# ProDocument_V3_2024-06-08.net
KiCad netlist of a schematic drawn in EasyEDA Pro
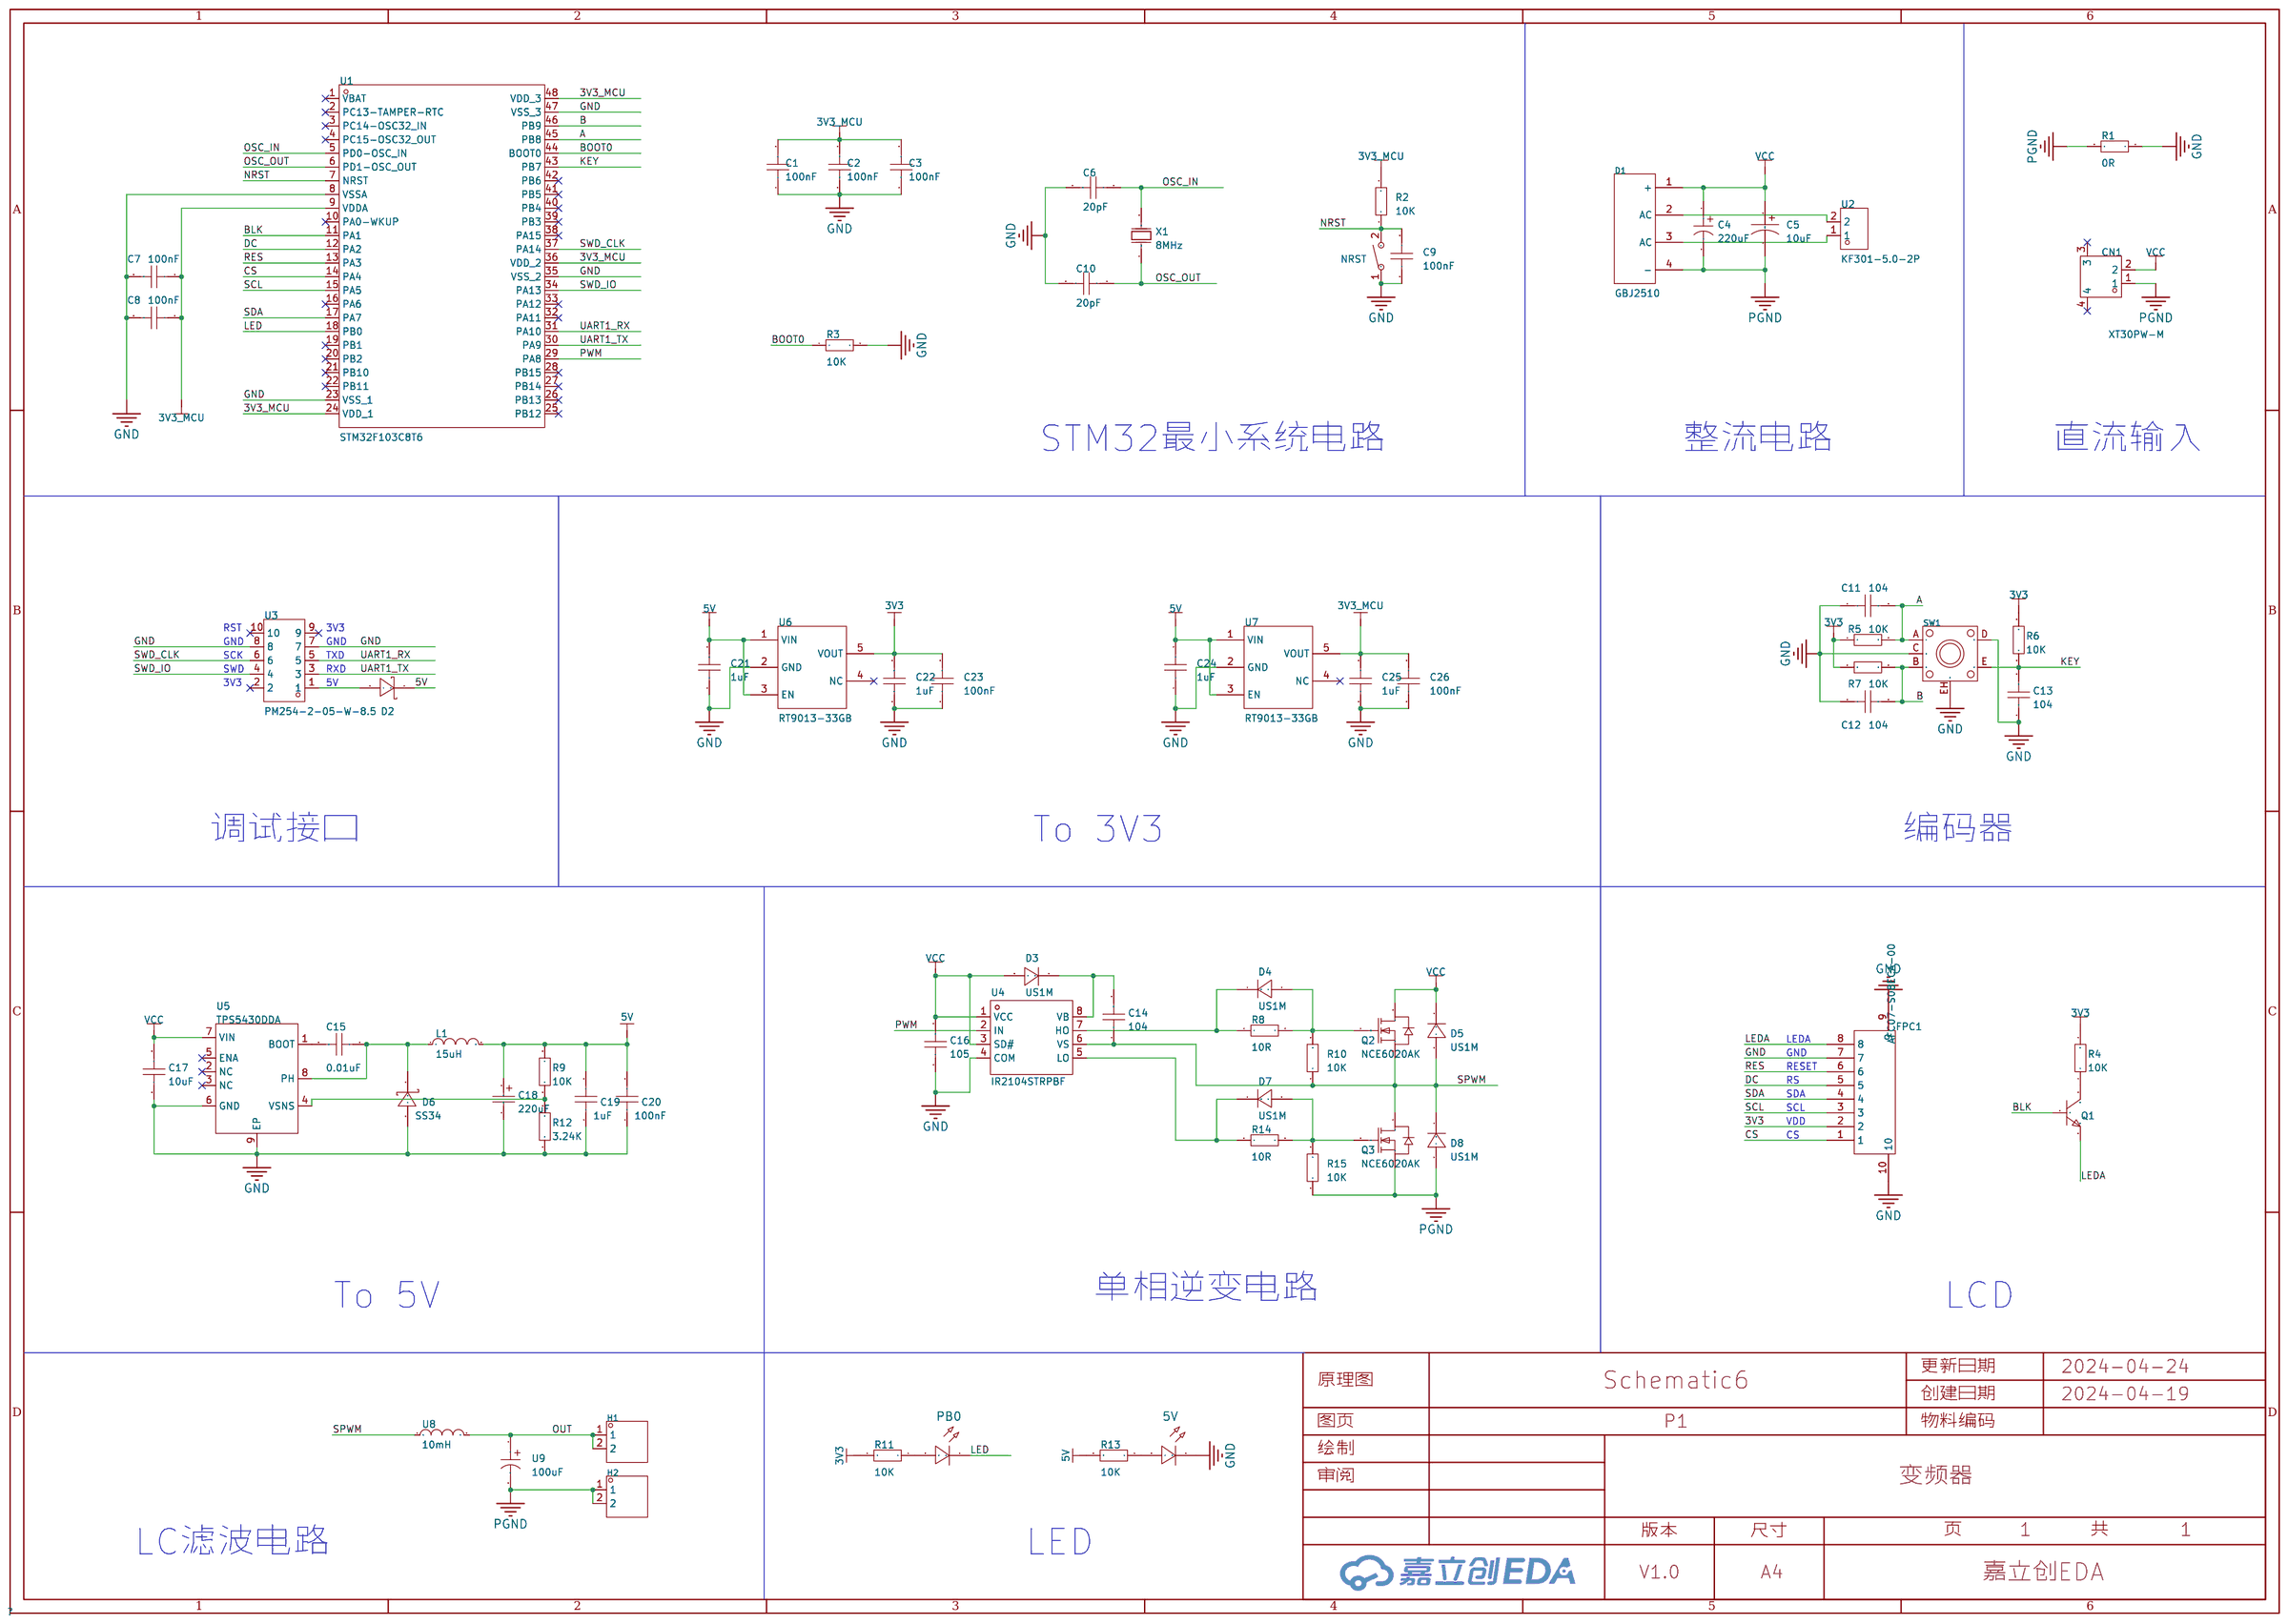
[diagram p0: schematic sheet]

(export (version "E")
  (design (tool "Eeschema 10.0.6"))
  (components
    (comp (ref "5V")
      (value "~")
      (footprint "easyedapro:LED_0603")
      (libsource (lib "easyedapro") (part "LED_R"))
    )
    (comp (ref "C1")
      (value "100nF")
      (footprint "easyedapro:C0603")
      (libsource (lib "easyedapro") (part "CapAcitance"))
    )
    (comp (ref "C2")
      (value "100nF")
      (footprint "easyedapro:C0603")
      (libsource (lib "easyedapro") (part "CapAcitance"))
    )
    (comp (ref "C3")
      (value "100nF")
      (footprint "easyedapro:C0603")
      (libsource (lib "easyedapro") (part "CapAcitance"))
    )
    (comp (ref "C4")
      (value "220uF")
      (footprint "easyedapro:CAP-TH_BD8.0-P3.50-D0.6-FD")
      (description "容值:220uF;精度:±20%;额定电压:50V;纹波电流:350mA@120kHz;等效串联电阻:-;")
      (fields (field (name "Manufacturer Part") "01EC3470") (field (name "Manufacturer") "KNSCHA(科尼盛)"))
      (libsource (lib "easyedapro") (part "01EC3470"))
    )
    (comp (ref "C5")
      (value "10uF")
      (footprint "easyedapro:CAP-TH_BD5.0-P2.00-D0.8-FD")
      (description "容值:10uF;精度:±20%;额定电压:50V;纹波电流:50mA@120Hz;等效串联电阻:-;")
      (fields
        (field (name "Manufacturer Part") "01EC1809SHC10UF50V")
        (field (name "Manufacturer") "KNSCHA(科尼盛)")
      )
      (libsource (lib "easyedapro") (part "01EC1809SHC10UF50V"))
    )
    (comp (ref "C6")
      (value "20pF")
      (footprint "easyedapro:C0603")
      (libsource (lib "easyedapro") (part "CapAcitance"))
    )
    (comp (ref "C7")
      (value "100nF")
      (footprint "easyedapro:C0603")
      (libsource (lib "easyedapro") (part "CapAcitance"))
    )
    (comp (ref "C8")
      (value "100nF")
      (footprint "easyedapro:C0603")
      (libsource (lib "easyedapro") (part "CapAcitance"))
    )
    (comp (ref "C9")
      (value "100nF")
      (footprint "easyedapro:C0603")
      (libsource (lib "easyedapro") (part "CapAcitance"))
    )
    (comp (ref "C10")
      (value "20pF")
      (footprint "easyedapro:C0603")
      (libsource (lib "easyedapro") (part "CapAcitance"))
    )
    (comp (ref "C11")
      (value "104")
      (footprint "easyedapro:C0603")
      (libsource (lib "easyedapro") (part "CapAcitance"))
    )
    (comp (ref "C12")
      (value "104")
      (footprint "easyedapro:C0603")
      (libsource (lib "easyedapro") (part "CapAcitance"))
    )
    (comp (ref "C13")
      (value "104")
      (footprint "easyedapro:C0603")
      (libsource (lib "easyedapro") (part "CapAcitance"))
    )
    (comp (ref "C14")
      (value "104")
      (footprint "easyedapro:C0603")
      (libsource (lib "easyedapro") (part "CapAcitance"))
    )
    (comp (ref "C15")
      (value "100nF")
      (footprint "easyedapro:C0603")
      (libsource (lib "easyedapro") (part "CapAcitance"))
    )
    (comp (ref "C16")
      (value "105")
      (footprint "easyedapro:C0603")
      (libsource (lib "easyedapro") (part "CapAcitance"))
    )
    (comp (ref "C17")
      (value "100nF")
      (footprint "easyedapro:C0603")
      (libsource (lib "easyedapro") (part "CapAcitance"))
    )
    (comp (ref "C18")
      (value "220uF")
      (footprint "easyedapro:CASE-D_7343")
      (description "容值:220uF;精度:±10%;额定电压:10V;等效串联电阻:500mΩ@100kHz;")
      (fields (field (name "Manufacturer Part") "TAJD227K010RNJ") (field (name "Manufacturer") "Kyocera AVX"))
      (libsource (lib "easyedapro") (part "TAJD227K010RNJ"))
    )
    (comp (ref "C19") (value "100nF") (libsource (lib "easyedapro") (part "c1210x7r475k630nt")))
    (comp (ref "C20") (value "100nF") (libsource (lib "easyedapro") (part "c1210x7r475k630nt")))
    (comp (ref "C21") (value "100nF") (libsource (lib "easyedapro") (part "c1210x7r475k630nt")))
    (comp (ref "C22") (value "100nF") (libsource (lib "easyedapro") (part "c1210x7r475k630nt")))
    (comp (ref "C23") (value "100nF") (libsource (lib "easyedapro") (part "c1210x7r475k630nt")))
    (comp (ref "C24") (value "100nF") (libsource (lib "easyedapro") (part "c1210x7r475k630nt")))
    (comp (ref "C25") (value "100nF") (libsource (lib "easyedapro") (part "c1210x7r475k630nt")))
    (comp (ref "C26") (value "100nF") (libsource (lib "easyedapro") (part "c1210x7r475k630nt")))
    (comp (ref "CN1")
      (value "XT30PW-M")
      (footprint "easyedapro:CONN-TH_XT30PW-M")
      (description "Socket,DCsupply,XT30,male,PIN:2")
      (fields (field (name "Manufacturer") "AMASS(艾迈斯)"))
      (libsource (lib "easyedapro") (part "XT30PW-M"))
    )
    (comp (ref "D1")
      (value "GBJ2510")
      (footprint "easyedapro:DIO-BG-TH_PB")
      (description "正向压降(Vf):1.05V@12.5A;直流反向耐压(Vr):1kV;平均整流电流(Io):25A;正向浪涌电流(Ifsm):350A;")
      (fields (field (name "Manufacturer") "MDD"))
      (libsource (lib "easyedapro") (part "GBJ2510"))
    )
    (comp (ref "D2")
      (value "1N5819WS")
      (footprint "easyedapro:SOD-323_L1.8-W1.3-LS2.5-RD")
      (description "正向压降(Vf):600mV@1A;直流反向耐压(Vr):40V;平均整流电流(Io):1A;")
      (fields (field (name "Manufacturer") "Hottech(合科泰)"))
      (libsource (lib "easyedapro") (part "1N5819WS"))
    )
    (comp (ref "D3")
      (value "US1M")
      (footprint "easyedapro:SMA_L4.4-W2.8-LS5.4-RD")
      (description "二极管配置:独立式;正向压降(Vf):1.7V@1A;直流反向耐压(Vr):1kV;平均整流电流(Io):1A;反向恢复时间(trr):75ns;")
      (fields (field (name "Manufacturer") "MDD"))
      (libsource (lib "easyedapro") (part "US1MG_C412437"))
    )
    (comp (ref "D4")
      (value "US1M")
      (footprint "easyedapro:SMA_L4.4-W2.8-LS5.4-RD")
      (description "二极管配置:独立式;正向压降(Vf):1.7V@1A;直流反向耐压(Vr):1kV;平均整流电流(Io):1A;反向恢复时间(trr):75ns;")
      (fields (field (name "Manufacturer") "MDD"))
      (libsource (lib "easyedapro") (part "US1MG_C412437"))
    )
    (comp (ref "D5")
      (value "US1M")
      (footprint "easyedapro:SMA_L4.4-W2.8-LS5.4-RD")
      (description "二极管配置:独立式;正向压降(Vf):1.7V@1A;直流反向耐压(Vr):1kV;平均整流电流(Io):1A;反向恢复时间(trr):75ns;")
      (fields (field (name "Manufacturer") "MDD"))
      (libsource (lib "easyedapro") (part "US1MG_C412437"))
    )
    (comp (ref "D6")
      (value "SS34")
      (footprint "easyedapro:SMA_L4.3-W2.6-LS5.2-RD")
      (description "二极管配置:独立式;直流反向耐压(Vr):40V;平均整流电流(Io):3A;正向压降(Vf):550mV@3A;反向电流(Ir):500uA@40V;")
      (fields (field (name "Manufacturer") "MDD"))
      (libsource (lib "easyedapro") (part "SS34_C8678"))
    )
    (comp (ref "D7")
      (value "US1M")
      (footprint "easyedapro:SMA_L4.4-W2.8-LS5.4-RD")
      (description "二极管配置:独立式;正向压降(Vf):1.7V@1A;直流反向耐压(Vr):1kV;平均整流电流(Io):1A;反向恢复时间(trr):75ns;")
      (fields (field (name "Manufacturer") "MDD"))
      (libsource (lib "easyedapro") (part "US1MG_C412437"))
    )
    (comp (ref "D8")
      (value "US1M")
      (footprint "easyedapro:SMA_L4.4-W2.8-LS5.4-RD")
      (description "二极管配置:独立式;正向压降(Vf):1.7V@1A;直流反向耐压(Vr):1kV;平均整流电流(Io):1A;反向恢复时间(trr):75ns;")
      (fields (field (name "Manufacturer") "MDD"))
      (libsource (lib "easyedapro") (part "US1MG_C412437"))
    )
    (comp (ref "FPC1")
      (value "AFC07-S08ECA-00")
      (footprint "easyedapro:FPC-SMD_P0.5-8P_LCS-SH-H2.0")
      (description "间距:0.5mm;触点数量:8P;锁定特性:抽屉式;触点类型:上接;安装类型:卧贴;")
      (fields (field (name "Manufacturer") "JS(钜硕电子)"))
      (libsource (lib "easyedapro") (part "AFC07-S08ECA-00"))
    )
    (comp (ref "H1")
      (value "~")
      (footprint "easyedapro:HDR-TH_2P-P2.54-V-M-1")
      (libsource (lib "easyedapro") (part "210S-1*2P L=11.6MMGold-plated black"))
    )
    (comp (ref "H2")
      (value "~")
      (footprint "easyedapro:HDR-TH_2P-P2.54-V-M-1")
      (libsource (lib "easyedapro") (part "210S-1*2P L=11.6MMGold-plated black"))
    )
    (comp (ref "L1")
      (value "15uH")
      (footprint "easyedapro:IND-SMD_L7.0-W6.6_FXL0630")
      (description "电感值:15uH;精度:±20%;额定电流:3A;饱和电流(Isat):4.5A;类型:一体成型电感;")
      (fields (field (name "Manufacturer Part") "FXL0630-150-M") (field (name "Manufacturer") "cjiang(长江微电)"))
      (libsource (lib "easyedapro") (part "FXL0630-150-M"))
    )
    (comp (ref "NRST")
      (value "TS-1071AD-A1B3-D4")
      (footprint "easyedapro:SW-SMD_L4.0-W3.0-LS4.8")
      (description "电路结构:单刀单掷;按钮形状:圆形按钮;作用力:250gf;安装方式:-;开关长度:4mm;开关宽度:3mm;开关高度:2mm;带灯:-;机械寿命:-;")
      (fields (field (name "Manufacturer") "Yuandi(元迪)"))
      (libsource (lib "easyedapro") (part "TS-1071AD-A1B3-D4"))
    )
    (comp (ref "PB0")
      (value "~")
      (footprint "easyedapro:LED_0603")
      (libsource (lib "easyedapro") (part "LED_R"))
    )
    (comp (ref "Q1")
      (value "~")
      (footprint "easyedapro:S8050_SOT-23")
      (libsource (lib "easyedapro") (part "NPN"))
    )
    (comp (ref "Q2")
      (value "NCE6020AK")
      (footprint "easyedapro:TO-252-2_L6.6-W6.1-P4.57-LS10.1-TL-CW")
      (fields (field (name "Manufacturer") "NCE(无锡新洁能)"))
      (libsource (lib "easyedapro") (part "NCE6020AK"))
    )
    (comp (ref "Q3")
      (value "NCE6020AK")
      (footprint "easyedapro:TO-252-2_L6.6-W6.1-P4.57-LS10.1-TL-CW")
      (fields (field (name "Manufacturer") "NCE(无锡新洁能)"))
      (libsource (lib "easyedapro") (part "NCE6020AK"))
    )
    (comp (ref "R1") (value "0R") (footprint "easyedapro:R0603") (libsource (lib "easyedapro") (part "电阻")))
    (comp (ref "R2") (value "10K") (footprint "easyedapro:R0603") (libsource (lib "easyedapro") (part "电阻")))
    (comp (ref "R3") (value "10K") (footprint "easyedapro:R0603") (libsource (lib "easyedapro") (part "电阻")))
    (comp (ref "R4") (value "10K") (footprint "easyedapro:R0603") (libsource (lib "easyedapro") (part "电阻")))
    (comp (ref "R5") (value "10K") (footprint "easyedapro:R0603") (libsource (lib "easyedapro") (part "电阻")))
    (comp (ref "R6") (value "10K") (footprint "easyedapro:R0603") (libsource (lib "easyedapro") (part "电阻")))
    (comp (ref "R7") (value "10K") (footprint "easyedapro:R0603") (libsource (lib "easyedapro") (part "电阻")))
    (comp (ref "R8") (value "10R") (footprint "easyedapro:R0603") (libsource (lib "easyedapro") (part "电阻")))
    (comp (ref "R9") (value "10K") (footprint "easyedapro:R0603") (libsource (lib "easyedapro") (part "电阻")))
    (comp (ref "R10") (value "10K") (footprint "easyedapro:R0603") (libsource (lib "easyedapro") (part "电阻")))
    (comp (ref "R11") (value "10K") (footprint "easyedapro:R0603") (libsource (lib "easyedapro") (part "电阻")))
    (comp (ref "R12") (value "10K") (footprint "easyedapro:R0603") (libsource (lib "easyedapro") (part "电阻")))
    (comp (ref "R13") (value "10K") (footprint "easyedapro:R0603") (libsource (lib "easyedapro") (part "电阻")))
    (comp (ref "R14") (value "10R") (footprint "easyedapro:R0603") (libsource (lib "easyedapro") (part "电阻")))
    (comp (ref "R15") (value "10K") (footprint "easyedapro:R0603") (libsource (lib "easyedapro") (part "电阻")))
    (comp (ref "SW1")
      (value "EC11N1520401")
      (footprint "easyedapro:SW-TH_EC11NXXXX")
      (fields (field (name "Manufacturer") "ALPSALPINE(阿尔卑斯阿尔派)"))
      (libsource (lib "easyedapro") (part "EC11N1520401"))
    )
    (comp (ref "U1")
      (value "STM32F103C8T6")
      (footprint "easyedapro:LQFP-48_L7.0-W7.0-P0.50-LS9.0-BL")
      (description "CPU内核:CM3;程序存储容量:64KB;RAM总容量:20KB;GPIO端口数量:37;工作电压范围:2V~3.6V;CPU最大主频:72MHz;程序存储器类型:FLASH;")
      (fields (field (name "Manufacturer") "ST(意法半导体)"))
      (libsource (lib "easyedapro") (part "STM32F103C8T6"))
    )
    (comp (ref "U2")
      (value "KF301-5.0-2P")
      (footprint "easyedapro:CONN-TH_P5.00_KF301-5.0-2P")
      (fields (field (name "Manufacturer") "KEFA(科发)"))
      (libsource (lib "easyedapro") (part "KF301-5.0-2P"))
    )
    (comp (ref "U3")
      (value "PM254-2-05-W-8.5")
      (footprint "easyedapro:HDR-TH_10P-P2.54-H-F-R2-C5-W8.5")
      (fields (field (name "Manufacturer") "HCTL(华灿天禄)"))
      (libsource (lib "easyedapro") (part "PM254-2-05-W-8.5"))
    )
    (comp (ref "U4")
      (value "IR2104STRPBF")
      (footprint "easyedapro:SOIC-8_L4.9-W3.9-P1.27-LS6.0-BL")
      (description "驱动配置:半桥;负载类型:MOSFET；IGBT;驱动通道数:2;峰值灌电流:360mA;峰值拉电流:210mA;电源电压:10V~20V;上升时间:100ns;下降时间:50ns;")
      (fields (field (name "Manufacturer") "Infineon(英飞凌)"))
      (libsource (lib "easyedapro") (part "IR2104STRPBF"))
    )
    (comp (ref "U5")
      (value "TPS5430DDA")
      (footprint "easyedapro:ESOP-8_L4.9-W3.9-P1.27-LS6.0-BL-EP-2")
      (fields (field (name "Manufacturer") "TI(德州仪器)"))
      (libsource (lib "easyedapro") (part "TPS5430DDA"))
    )
    (comp (ref "U6")
      (value "RT9013-33GB")
      (footprint "easyedapro:SOT-23-5_L3.0-W1.7-P0.95-LS2.8-BL")
      (description "输出类型:固定;最大输入电压:5.5V;输出电压:3.3V;最大输出电流:500mA;电源纹波抑制比(PSRR):50dB@(10kHz);输出极性:正极;")
      (fields (field (name "Manufacturer") "RICHTEK(立锜)"))
      (libsource (lib "easyedapro") (part "RT9013-33GB"))
    )
    (comp (ref "U7")
      (value "RT9013-33GB")
      (footprint "easyedapro:SOT-23-5_L3.0-W1.7-P0.95-LS2.8-BL")
      (description "输出类型:固定;最大输入电压:5.5V;输出电压:3.3V;最大输出电流:500mA;电源纹波抑制比(PSRR):50dB@(10kHz);输出极性:正极;")
      (fields (field (name "Manufacturer") "RICHTEK(立锜)"))
      (libsource (lib "easyedapro") (part "RT9013-33GB"))
    )
    (comp (ref "U8")
      (value "10mH")
      (footprint "easyedapro:IND-TH_BD10.0-P5.00-D0.6")
      (description "电感值:100uH;精度:±10%;类型:工字电感;")
      (fields (field (name "Manufacturer Part") "XR8*10-101K-L") (field (name "Manufacturer") "XR(祥如)"))
      (libsource (lib "easyedapro") (part "XR8*10-101K-L"))
    )
    (comp (ref "U9")
      (value "100uF")
      (footprint "easyedapro:CAP-TH_BD8.0-P3.50-D0.6-FD")
      (description "容值:470uF;精度:±20%;额定电压:16V;")
      (fields (field (name "Manufacturer Part") "8471LCM0812LEN91EC") (field (name "Manufacturer") "FH(风华)"))
      (libsource (lib "easyedapro") (part "8471LCM0812LEN91EC"))
    )
    (comp (ref "X1")
      (value "8MHz")
      (footprint "easyedapro:CRYSTAL-SMD_L5.0-W3.2")
      (description "晶振类型:贴片晶振;频率:8MHz;常温频差:±10ppm;外接负载电容:20pF;频率稳定度(全温):±20ppm;")
      (fields (field (name "Manufacturer Part") "X50328MSB2GI") (field (name "Manufacturer") "YXC(扬兴晶振)"))
      (libsource (lib "easyedapro") (part "X50328MSB2GI"))
    )
  )
  (nets
    (net (code "1") (name "/A") (class "Default")
      (node (ref "C11") (pin "2") (pinfunction "2_2") (pintype "input"))
      (node (ref "R5") (pin "2") (pinfunction "2_2") (pintype "input"))
      (node (ref "SW1") (pin "A") (pinfunction "A_A") (pintype "input"))
      (node (ref "U1") (pin "45") (pinfunction "PB8_45") (pintype "unspecified"))
    )
    (net (code "2") (name "/B") (class "Default")
      (node (ref "C12") (pin "2") (pinfunction "2_2") (pintype "input"))
      (node (ref "R7") (pin "2") (pinfunction "2_2") (pintype "input"))
      (node (ref "SW1") (pin "B") (pinfunction "B_B") (pintype "input"))
      (node (ref "U1") (pin "46") (pinfunction "PB9_46") (pintype "unspecified"))
    )
    (net (code "3") (name "/BLK") (class "Default")
      (node (ref "Q1") (pin "1") (pinfunction "1_1") (pintype "unspecified"))
      (node (ref "U1") (pin "11") (pinfunction "PA1_11") (pintype "unspecified"))
    )
    (net (code "4") (name "/BOOT0") (class "Default")
      (node (ref "R3") (pin "1") (pinfunction "1_1") (pintype "input"))
      (node (ref "U1") (pin "44") (pinfunction "BOOT0_44") (pintype "unspecified"))
    )
    (net (code "5") (name "/CS") (class "Default")
      (node (ref "FPC1") (pin "1") (pinfunction "1_1") (pintype "unspecified"))
      (node (ref "U1") (pin "14") (pinfunction "PA4_14") (pintype "unspecified"))
    )
    (net (code "6") (name "/DC") (class "Default")
      (node (ref "FPC1") (pin "5") (pinfunction "5_5") (pintype "unspecified"))
      (node (ref "U1") (pin "12") (pinfunction "PA2_12") (pintype "unspecified"))
    )
    (net (code "7") (name "/KEY") (class "Default")
      (node (ref "C13") (pin "2") (pinfunction "2_2") (pintype "input"))
      (node (ref "R6") (pin "1") (pinfunction "1_1") (pintype "input"))
      (node (ref "SW1") (pin "E") (pinfunction "E_E") (pintype "input"))
      (node (ref "U1") (pin "43") (pinfunction "PB7_43") (pintype "unspecified"))
    )
    (net (code "8") (name "/LED") (class "Default")
      (node (ref "PB0") (pin "1") (pinfunction "C_1") (pintype "input"))
      (node (ref "U1") (pin "18") (pinfunction "PB0_18") (pintype "unspecified"))
    )
    (net (code "9") (name "/LEDA") (class "Default")
      (node (ref "FPC1") (pin "8") (pinfunction "8_8") (pintype "unspecified"))
      (node (ref "Q1") (pin "2") (pinfunction "2_2") (pintype "unspecified"))
    )
    (net (code "10") (name "/NRST") (class "Default")
      (node (ref "C9") (pin "2") (pinfunction "2_2") (pintype "input"))
      (node (ref "NRST") (pin "2") (pinfunction "2_2") (pintype "unspecified"))
      (node (ref "R2") (pin "1") (pinfunction "1_1") (pintype "input"))
      (node (ref "U1") (pin "7") (pinfunction "NRST_7") (pintype "unspecified"))
    )
    (net (code "11") (name "/OSC_IN") (class "Default")
      (node (ref "C6") (pin "1") (pinfunction "1_1") (pintype "input"))
      (node (ref "U1") (pin "5") (pinfunction "PD0-OSC_IN_5") (pintype "unspecified"))
      (node (ref "X1") (pin "2") (pinfunction "OSC2_2") (pintype "input"))
    )
    (net (code "12") (name "/OSC_OUT") (class "Default")
      (node (ref "C10") (pin "1") (pinfunction "1_1") (pintype "input"))
      (node (ref "U1") (pin "6") (pinfunction "PD1-OSC_OUT_6") (pintype "unspecified"))
      (node (ref "X1") (pin "1") (pinfunction "OSC1_1") (pintype "input"))
    )
    (net (code "13") (name "/OUT") (class "Default")
      (node (ref "H1") (pin "1") (pinfunction "1_1") (pintype "input"))
      (node (ref "H1") (pin "2") (pinfunction "2_2") (pintype "input"))
      (node (ref "U8") (pin "2") (pinfunction "2_2") (pintype "unspecified"))
      (node (ref "U9") (pin "1") (pinfunction "1_1") (pintype "input"))
    )
    (net (code "14") (name "/PWM") (class "Default")
      (node (ref "U1") (pin "29") (pinfunction "PA8_29") (pintype "unspecified"))
      (node (ref "U4") (pin "2") (pinfunction "IN_2") (pintype "unspecified"))
    )
    (net (code "15") (name "/RES") (class "Default")
      (node (ref "FPC1") (pin "6") (pinfunction "6_6") (pintype "unspecified"))
      (node (ref "U1") (pin "13") (pinfunction "PA3_13") (pintype "unspecified"))
    )
    (net (code "16") (name "/SCL") (class "Default")
      (node (ref "FPC1") (pin "3") (pinfunction "3_3") (pintype "unspecified"))
      (node (ref "U1") (pin "15") (pinfunction "PA5_15") (pintype "unspecified"))
    )
    (net (code "17") (name "/SDA") (class "Default")
      (node (ref "FPC1") (pin "4") (pinfunction "4_4") (pintype "unspecified"))
      (node (ref "U1") (pin "17") (pinfunction "PA7_17") (pintype "unspecified"))
    )
    (net (code "18") (name "/SPWM") (class "Default")
      (node (ref "C14") (pin "1") (pinfunction "1_1") (pintype "input"))
      (node (ref "D5") (pin "2") (pinfunction "A_2") (pintype "unspecified"))
      (node (ref "D8") (pin "1") (pinfunction "C_1") (pintype "unspecified"))
      (node (ref "Q2") (pin "3") (pinfunction "S_3") (pintype "input"))
      (node (ref "Q3") (pin "2") (pinfunction "D_2") (pintype "input"))
      (node (ref "R10") (pin "1") (pinfunction "1_1") (pintype "input"))
      (node (ref "U4") (pin "6") (pinfunction "VS_6") (pintype "unspecified"))
      (node (ref "U8") (pin "1") (pinfunction "1_1") (pintype "unspecified"))
    )
    (net (code "19") (name "/SWD_CLK") (class "Default")
      (node (ref "U1") (pin "37") (pinfunction "PA14_37") (pintype "unspecified"))
      (node (ref "U3") (pin "6") (pinfunction "6_6") (pintype "unspecified"))
    )
    (net (code "20") (name "/SWD_IO") (class "Default")
      (node (ref "U1") (pin "34") (pinfunction "PA13_34") (pintype "unspecified"))
      (node (ref "U3") (pin "4") (pinfunction "4_4") (pintype "unspecified"))
    )
    (net (code "21") (name "/UART1_RX") (class "Default")
      (node (ref "U1") (pin "31") (pinfunction "PA10_31") (pintype "unspecified"))
      (node (ref "U3") (pin "5") (pinfunction "5_5") (pintype "unspecified"))
    )
    (net (code "22") (name "/UART1_TX") (class "Default")
      (node (ref "U1") (pin "30") (pinfunction "PA9_30") (pintype "unspecified"))
      (node (ref "U3") (pin "3") (pinfunction "3_3") (pintype "unspecified"))
    )
    (net (code "23") (name "3V3") (class "Default")
      (node (ref "C22") (pin "2") (pinfunction "2_2") (pintype "input"))
      (node (ref "C23") (pin "2") (pinfunction "2_2") (pintype "input"))
      (node (ref "FPC1") (pin "2") (pinfunction "2_2") (pintype "unspecified"))
      (node (ref "R11") (pin "2") (pinfunction "2_2") (pintype "input"))
      (node (ref "R4") (pin "2") (pinfunction "2_2") (pintype "input"))
      (node (ref "R5") (pin "1") (pinfunction "1_1") (pintype "input"))
      (node (ref "R6") (pin "2") (pinfunction "2_2") (pintype "input"))
      (node (ref "R7") (pin "1") (pinfunction "1_1") (pintype "input"))
      (node (ref "U6") (pin "5") (pinfunction "VOUT_5") (pintype "unspecified"))
    )
    (net (code "24") (name "3V3_MCU") (class "Default")
      (node (ref "C1") (pin "2") (pinfunction "2_2") (pintype "input"))
      (node (ref "C2") (pin "2") (pinfunction "2_2") (pintype "input"))
      (node (ref "C25") (pin "2") (pinfunction "2_2") (pintype "input"))
      (node (ref "C26") (pin "2") (pinfunction "2_2") (pintype "input"))
      (node (ref "C3") (pin "2") (pinfunction "2_2") (pintype "input"))
      (node (ref "C7") (pin "1") (pinfunction "1_1") (pintype "input"))
      (node (ref "C8") (pin "1") (pinfunction "1_1") (pintype "input"))
      (node (ref "R2") (pin "2") (pinfunction "2_2") (pintype "input"))
      (node (ref "U1") (pin "24") (pinfunction "VDD_1_24") (pintype "unspecified"))
      (node (ref "U1") (pin "36") (pinfunction "VDD_2_36") (pintype "unspecified"))
      (node (ref "U1") (pin "48") (pinfunction "VDD_3_48") (pintype "unspecified"))
      (node (ref "U1") (pin "9") (pinfunction "VDDA_9") (pintype "unspecified"))
      (node (ref "U7") (pin "5") (pinfunction "VOUT_5") (pintype "unspecified"))
    )
    (net (code "25") (name "5V") (class "Default")
      (node (ref "C18") (pin "1") (pinfunction "1_1") (pintype "input"))
      (node (ref "C19") (pin "2") (pinfunction "2_2") (pintype "input"))
      (node (ref "C20") (pin "2") (pinfunction "2_2") (pintype "input"))
      (node (ref "C21") (pin "2") (pinfunction "2_2") (pintype "input"))
      (node (ref "C24") (pin "2") (pinfunction "2_2") (pintype "input"))
      (node (ref "D2") (pin "1") (pinfunction "K_1") (pintype "unspecified"))
      (node (ref "L1") (pin "2") (pinfunction "2_2") (pintype "unspecified"))
      (node (ref "R13") (pin "2") (pinfunction "2_2") (pintype "input"))
      (node (ref "R9") (pin "2") (pinfunction "2_2") (pintype "input"))
      (node (ref "U6") (pin "1") (pinfunction "VIN_1") (pintype "unspecified"))
      (node (ref "U6") (pin "3") (pinfunction "EN_3") (pintype "unspecified"))
      (node (ref "U7") (pin "1") (pinfunction "VIN_1") (pintype "unspecified"))
      (node (ref "U7") (pin "3") (pinfunction "EN_3") (pintype "unspecified"))
    )
    (net (code "26") (name "GND") (class "Default")
      (node (ref "5V") (pin "1") (pinfunction "C_1") (pintype "input"))
      (node (ref "C1") (pin "1") (pinfunction "1_1") (pintype "input"))
      (node (ref "C10") (pin "2") (pinfunction "2_2") (pintype "input"))
      (node (ref "C11") (pin "1") (pinfunction "1_1") (pintype "input"))
      (node (ref "C12") (pin "1") (pinfunction "1_1") (pintype "input"))
      (node (ref "C13") (pin "1") (pinfunction "1_1") (pintype "input"))
      (node (ref "C16") (pin "1") (pinfunction "1_1") (pintype "input"))
      (node (ref "C17") (pin "1") (pinfunction "1_1") (pintype "input"))
      (node (ref "C18") (pin "2") (pinfunction "2_2") (pintype "input"))
      (node (ref "C19") (pin "1") (pinfunction "1_1") (pintype "input"))
      (node (ref "C2") (pin "1") (pinfunction "1_1") (pintype "input"))
      (node (ref "C20") (pin "1") (pinfunction "1_1") (pintype "input"))
      (node (ref "C21") (pin "1") (pinfunction "1_1") (pintype "input"))
      (node (ref "C22") (pin "1") (pinfunction "1_1") (pintype "input"))
      (node (ref "C23") (pin "1") (pinfunction "1_1") (pintype "input"))
      (node (ref "C24") (pin "1") (pinfunction "1_1") (pintype "input"))
      (node (ref "C25") (pin "1") (pinfunction "1_1") (pintype "input"))
      (node (ref "C26") (pin "1") (pinfunction "1_1") (pintype "input"))
      (node (ref "C3") (pin "1") (pinfunction "1_1") (pintype "input"))
      (node (ref "C6") (pin "2") (pinfunction "2_2") (pintype "input"))
      (node (ref "C7") (pin "2") (pinfunction "2_2") (pintype "input"))
      (node (ref "C8") (pin "2") (pinfunction "2_2") (pintype "input"))
      (node (ref "C9") (pin "1") (pinfunction "1_1") (pintype "input"))
      (node (ref "D6") (pin "2") (pinfunction "A_2") (pintype "input"))
      (node (ref "FPC1") (pin "10") (pinfunction "10_10") (pintype "unspecified"))
      (node (ref "FPC1") (pin "7") (pinfunction "7_7") (pintype "unspecified"))
      (node (ref "FPC1") (pin "9") (pinfunction "9_9") (pintype "unspecified"))
      (node (ref "NRST") (pin "1") (pinfunction "1_1") (pintype "unspecified"))
      (node (ref "R1") (pin "1") (pinfunction "1_1") (pintype "input"))
      (node (ref "R12") (pin "1") (pinfunction "1_1") (pintype "input"))
      (node (ref "R3") (pin "2") (pinfunction "2_2") (pintype "input"))
      (node (ref "SW1") (pin "C") (pinfunction "C_C") (pintype "input"))
      (node (ref "SW1") (pin "D") (pinfunction "D_D") (pintype "input"))
      (node (ref "SW1") (pin "EH") (pinfunction "EH_EH") (pintype "input"))
      (node (ref "U1") (pin "23") (pinfunction "VSS_1_23") (pintype "unspecified"))
      (node (ref "U1") (pin "35") (pinfunction "VSS_2_35") (pintype "unspecified"))
      (node (ref "U1") (pin "47") (pinfunction "VSS_3_47") (pintype "unspecified"))
      (node (ref "U1") (pin "8") (pinfunction "VSSA_8") (pintype "unspecified"))
      (node (ref "U3") (pin "7") (pinfunction "7_7") (pintype "unspecified"))
      (node (ref "U3") (pin "8") (pinfunction "8_8") (pintype "unspecified"))
      (node (ref "U4") (pin "4") (pinfunction "COM_4") (pintype "unspecified"))
      (node (ref "U5") (pin "6") (pinfunction "GND_6") (pintype "input"))
      (node (ref "U5") (pin "9") (pinfunction "EP_9") (pintype "input"))
      (node (ref "U6") (pin "2") (pinfunction "GND_2") (pintype "unspecified"))
      (node (ref "U7") (pin "2") (pinfunction "GND_2") (pintype "unspecified"))
    )
    (net (code "27") (name "Net-(5V-A)") (class "Default")
      (node (ref "5V") (pin "2") (pinfunction "A_2") (pintype "input"))
      (node (ref "R13") (pin "1") (pinfunction "1_1") (pintype "input"))
    )
    (net (code "28") (name "Net-(D1-AC-Pad2)") (class "Default")
      (node (ref "D1") (pin "2") (pinfunction "AC_2") (pintype "input"))
      (node (ref "U2") (pin "2") (pinfunction "2_2") (pintype "unspecified"))
    )
    (net (code "29") (name "Net-(D1-AC-Pad3)") (class "Default")
      (node (ref "D1") (pin "3") (pinfunction "AC_3") (pintype "input"))
      (node (ref "U2") (pin "1") (pinfunction "1_1") (pintype "unspecified"))
    )
    (net (code "30") (name "Net-(D2-A)") (class "Default")
      (node (ref "D2") (pin "2") (pinfunction "A_2") (pintype "unspecified"))
      (node (ref "U3") (pin "1") (pinfunction "1_1") (pintype "unspecified"))
    )
    (net (code "31") (name "Net-(D3-C)") (class "Default")
      (node (ref "C14") (pin "2") (pinfunction "2_2") (pintype "input"))
      (node (ref "D3") (pin "1") (pinfunction "C_1") (pintype "unspecified"))
      (node (ref "U4") (pin "8") (pinfunction "VB_8") (pintype "unspecified"))
    )
    (net (code "32") (name "Net-(D4-A)") (class "Default")
      (node (ref "D4") (pin "2") (pinfunction "A_2") (pintype "unspecified"))
      (node (ref "Q2") (pin "1") (pinfunction "G_1") (pintype "input"))
      (node (ref "R10") (pin "2") (pinfunction "2_2") (pintype "input"))
      (node (ref "R8") (pin "2") (pinfunction "2_2") (pintype "input"))
    )
    (net (code "33") (name "Net-(D4-C)") (class "Default")
      (node (ref "D4") (pin "1") (pinfunction "C_1") (pintype "unspecified"))
      (node (ref "R8") (pin "1") (pinfunction "1_1") (pintype "input"))
      (node (ref "U4") (pin "7") (pinfunction "HO_7") (pintype "unspecified"))
    )
    (net (code "34") (name "Net-(D6-K)") (class "Default")
      (node (ref "C15") (pin "1") (pinfunction "1_1") (pintype "input"))
      (node (ref "D6") (pin "1") (pinfunction "K_1") (pintype "input"))
      (node (ref "L1") (pin "1") (pinfunction "1_1") (pintype "unspecified"))
      (node (ref "U5") (pin "8") (pinfunction "PH_8") (pintype "input"))
    )
    (net (code "35") (name "Net-(D7-A)") (class "Default")
      (node (ref "D7") (pin "2") (pinfunction "A_2") (pintype "unspecified"))
      (node (ref "Q3") (pin "1") (pinfunction "G_1") (pintype "input"))
      (node (ref "R14") (pin "2") (pinfunction "2_2") (pintype "input"))
      (node (ref "R15") (pin "2") (pinfunction "2_2") (pintype "input"))
    )
    (net (code "36") (name "Net-(D7-C)") (class "Default")
      (node (ref "D7") (pin "1") (pinfunction "C_1") (pintype "unspecified"))
      (node (ref "R14") (pin "1") (pinfunction "1_1") (pintype "input"))
      (node (ref "U4") (pin "5") (pinfunction "LO_5") (pintype "unspecified"))
    )
    (net (code "37") (name "Net-(PB0-A)") (class "Default")
      (node (ref "PB0") (pin "2") (pinfunction "A_2") (pintype "input"))
      (node (ref "R11") (pin "1") (pinfunction "1_1") (pintype "input"))
    )
    (net (code "38") (name "Net-(Q1-Pad3)") (class "Default")
      (node (ref "Q1") (pin "3") (pinfunction "3_3") (pintype "unspecified"))
      (node (ref "R4") (pin "1") (pinfunction "1_1") (pintype "input"))
    )
    (net (code "39") (name "Net-(U5-BOOT)") (class "Default")
      (node (ref "C15") (pin "2") (pinfunction "2_2") (pintype "input"))
      (node (ref "U5") (pin "1") (pinfunction "BOOT_1") (pintype "input"))
    )
    (net (code "40") (name "Net-(U5-VSNS)") (class "Default")
      (node (ref "R12") (pin "2") (pinfunction "2_2") (pintype "input"))
      (node (ref "R9") (pin "1") (pinfunction "1_1") (pintype "input"))
      (node (ref "U5") (pin "4") (pinfunction "VSNS_4") (pintype "input"))
    )
    (net (code "41") (name "PGND") (class "Default")
      (node (ref "C4") (pin "2") (pinfunction "2_2") (pintype "input"))
      (node (ref "C5") (pin "2") (pinfunction "2_2") (pintype "unspecified"))
      (node (ref "CN1") (pin "1") (pinfunction "1_1") (pintype "input"))
      (node (ref "D1") (pin "4") (pinfunction "-_4") (pintype "input"))
      (node (ref "D8") (pin "2") (pinfunction "A_2") (pintype "unspecified"))
      (node (ref "H2") (pin "1") (pinfunction "1_1") (pintype "input"))
      (node (ref "H2") (pin "2") (pinfunction "2_2") (pintype "input"))
      (node (ref "Q3") (pin "3") (pinfunction "S_3") (pintype "input"))
      (node (ref "R1") (pin "2") (pinfunction "2_2") (pintype "input"))
      (node (ref "R15") (pin "1") (pinfunction "1_1") (pintype "input"))
      (node (ref "U9") (pin "2") (pinfunction "2_2") (pintype "input"))
    )
    (net (code "42") (name "VCC") (class "Default")
      (node (ref "C16") (pin "2") (pinfunction "2_2") (pintype "input"))
      (node (ref "C17") (pin "2") (pinfunction "2_2") (pintype "input"))
      (node (ref "C4") (pin "1") (pinfunction "1_1") (pintype "input"))
      (node (ref "C5") (pin "1") (pinfunction "1_1") (pintype "unspecified"))
      (node (ref "CN1") (pin "2") (pinfunction "2_2") (pintype "input"))
      (node (ref "D1") (pin "1") (pinfunction "+_1") (pintype "input"))
      (node (ref "D3") (pin "2") (pinfunction "A_2") (pintype "unspecified"))
      (node (ref "D5") (pin "1") (pinfunction "C_1") (pintype "unspecified"))
      (node (ref "Q2") (pin "2") (pinfunction "D_2") (pintype "input"))
      (node (ref "U4") (pin "1") (pinfunction "VCC_1") (pintype "unspecified"))
      (node (ref "U4") (pin "3") (pinfunction "SD#_3") (pintype "unspecified"))
      (node (ref "U5") (pin "7") (pinfunction "VIN_7") (pintype "input"))
    )
    (net (code "43") (name "unconnected-(CN1-Pad3)") (class "Default")
      (node (ref "CN1") (pin "3") (pinfunction "3_3") (pintype "input+no_connect"))
    )
    (net (code "44") (name "unconnected-(CN1-Pad4)") (class "Default")
      (node (ref "CN1") (pin "4") (pinfunction "4_4") (pintype "input+no_connect"))
    )
    (net (code "45") (name "unconnected-(U1-PA0-WKUP-Pad10)") (class "Default")
      (node (ref "U1") (pin "10") (pinfunction "PA0-WKUP_10") (pintype "unspecified+no_connect"))
    )
    (net (code "46") (name "unconnected-(U1-PA6-Pad16)") (class "Default")
      (node (ref "U1") (pin "16") (pinfunction "PA6_16") (pintype "unspecified+no_connect"))
    )
    (net (code "47") (name "unconnected-(U1-PA11-Pad32)") (class "Default")
      (node (ref "U1") (pin "32") (pinfunction "PA11_32") (pintype "unspecified+no_connect"))
    )
    (net (code "48") (name "unconnected-(U1-PA12-Pad33)") (class "Default")
      (node (ref "U1") (pin "33") (pinfunction "PA12_33") (pintype "unspecified+no_connect"))
    )
    (net (code "49") (name "unconnected-(U1-PA15-Pad38)") (class "Default")
      (node (ref "U1") (pin "38") (pinfunction "PA15_38") (pintype "unspecified+no_connect"))
    )
    (net (code "50") (name "unconnected-(U1-PB1-Pad19)") (class "Default")
      (node (ref "U1") (pin "19") (pinfunction "PB1_19") (pintype "unspecified+no_connect"))
    )
    (net (code "51") (name "unconnected-(U1-PB2-Pad20)") (class "Default")
      (node (ref "U1") (pin "20") (pinfunction "PB2_20") (pintype "unspecified+no_connect"))
    )
    (net (code "52") (name "unconnected-(U1-PB3-Pad39)") (class "Default")
      (node (ref "U1") (pin "39") (pinfunction "PB3_39") (pintype "unspecified+no_connect"))
    )
    (net (code "53") (name "unconnected-(U1-PB4-Pad40)") (class "Default")
      (node (ref "U1") (pin "40") (pinfunction "PB4_40") (pintype "unspecified+no_connect"))
    )
    (net (code "54") (name "unconnected-(U1-PB5-Pad41)") (class "Default")
      (node (ref "U1") (pin "41") (pinfunction "PB5_41") (pintype "unspecified+no_connect"))
    )
    (net (code "55") (name "unconnected-(U1-PB6-Pad42)") (class "Default")
      (node (ref "U1") (pin "42") (pinfunction "PB6_42") (pintype "unspecified+no_connect"))
    )
    (net (code "56") (name "unconnected-(U1-PB10-Pad21)") (class "Default")
      (node (ref "U1") (pin "21") (pinfunction "PB10_21") (pintype "unspecified+no_connect"))
    )
    (net (code "57") (name "unconnected-(U1-PB11-Pad22)") (class "Default")
      (node (ref "U1") (pin "22") (pinfunction "PB11_22") (pintype "unspecified+no_connect"))
    )
    (net (code "58") (name "unconnected-(U1-PB12-Pad25)") (class "Default")
      (node (ref "U1") (pin "25") (pinfunction "PB12_25") (pintype "unspecified+no_connect"))
    )
    (net (code "59") (name "unconnected-(U1-PB13-Pad26)") (class "Default")
      (node (ref "U1") (pin "26") (pinfunction "PB13_26") (pintype "unspecified+no_connect"))
    )
    (net (code "60") (name "unconnected-(U1-PB14-Pad27)") (class "Default")
      (node (ref "U1") (pin "27") (pinfunction "PB14_27") (pintype "unspecified+no_connect"))
    )
    (net (code "61") (name "unconnected-(U1-PB15-Pad28)") (class "Default")
      (node (ref "U1") (pin "28") (pinfunction "PB15_28") (pintype "unspecified+no_connect"))
    )
    (net (code "62") (name "unconnected-(U1-PC13-TAMPER-RTC-Pad2)") (class "Default")
      (node (ref "U1") (pin "2") (pinfunction "PC13-TAMPER-RTC_2") (pintype "unspecified+no_connect"))
    )
    (net (code "63") (name "unconnected-(U1-PC14-OSC32_IN-Pad3)") (class "Default")
      (node (ref "U1") (pin "3") (pinfunction "PC14-OSC32_IN_3") (pintype "unspecified+no_connect"))
    )
    (net (code "64") (name "unconnected-(U1-PC15-OSC32_OUT-Pad4)") (class "Default")
      (node (ref "U1") (pin "4") (pinfunction "PC15-OSC32_OUT_4") (pintype "unspecified+no_connect"))
    )
    (net (code "65") (name "unconnected-(U1-VBAT-Pad1)") (class "Default")
      (node (ref "U1") (pin "1") (pinfunction "VBAT_1") (pintype "unspecified+no_connect"))
    )
    (net (code "66") (name "unconnected-(U3-Pad2)") (class "Default")
      (node (ref "U3") (pin "2") (pinfunction "2_2") (pintype "unspecified+no_connect"))
    )
    (net (code "67") (name "unconnected-(U3-Pad9)") (class "Default")
      (node (ref "U3") (pin "9") (pinfunction "9_9") (pintype "unspecified+no_connect"))
    )
    (net (code "68") (name "unconnected-(U3-Pad10)") (class "Default")
      (node (ref "U3") (pin "10") (pinfunction "10_10") (pintype "unspecified+no_connect"))
    )
    (net (code "69") (name "unconnected-(U5-ENA-Pad5)") (class "Default")
      (node (ref "U5") (pin "5") (pinfunction "ENA_5") (pintype "input+no_connect"))
    )
    (net (code "70") (name "unconnected-(U5-NC-Pad2)") (class "Default")
      (node (ref "U5") (pin "2") (pinfunction "NC_2") (pintype "input+no_connect"))
    )
    (net (code "71") (name "unconnected-(U5-NC-Pad3)") (class "Default")
      (node (ref "U5") (pin "3") (pinfunction "NC_3") (pintype "input+no_connect"))
    )
    (net (code "72") (name "unconnected-(U6-NC-Pad4)") (class "Default")
      (node (ref "U6") (pin "4") (pinfunction "NC_4") (pintype "unspecified+no_connect"))
    )
    (net (code "73") (name "unconnected-(U7-NC-Pad4)") (class "Default")
      (node (ref "U7") (pin "4") (pinfunction "NC_4") (pintype "unspecified+no_connect"))
    )
  )
)
